# pid_driver.net
KiCad netlist of a schematic drawn in EAGLE
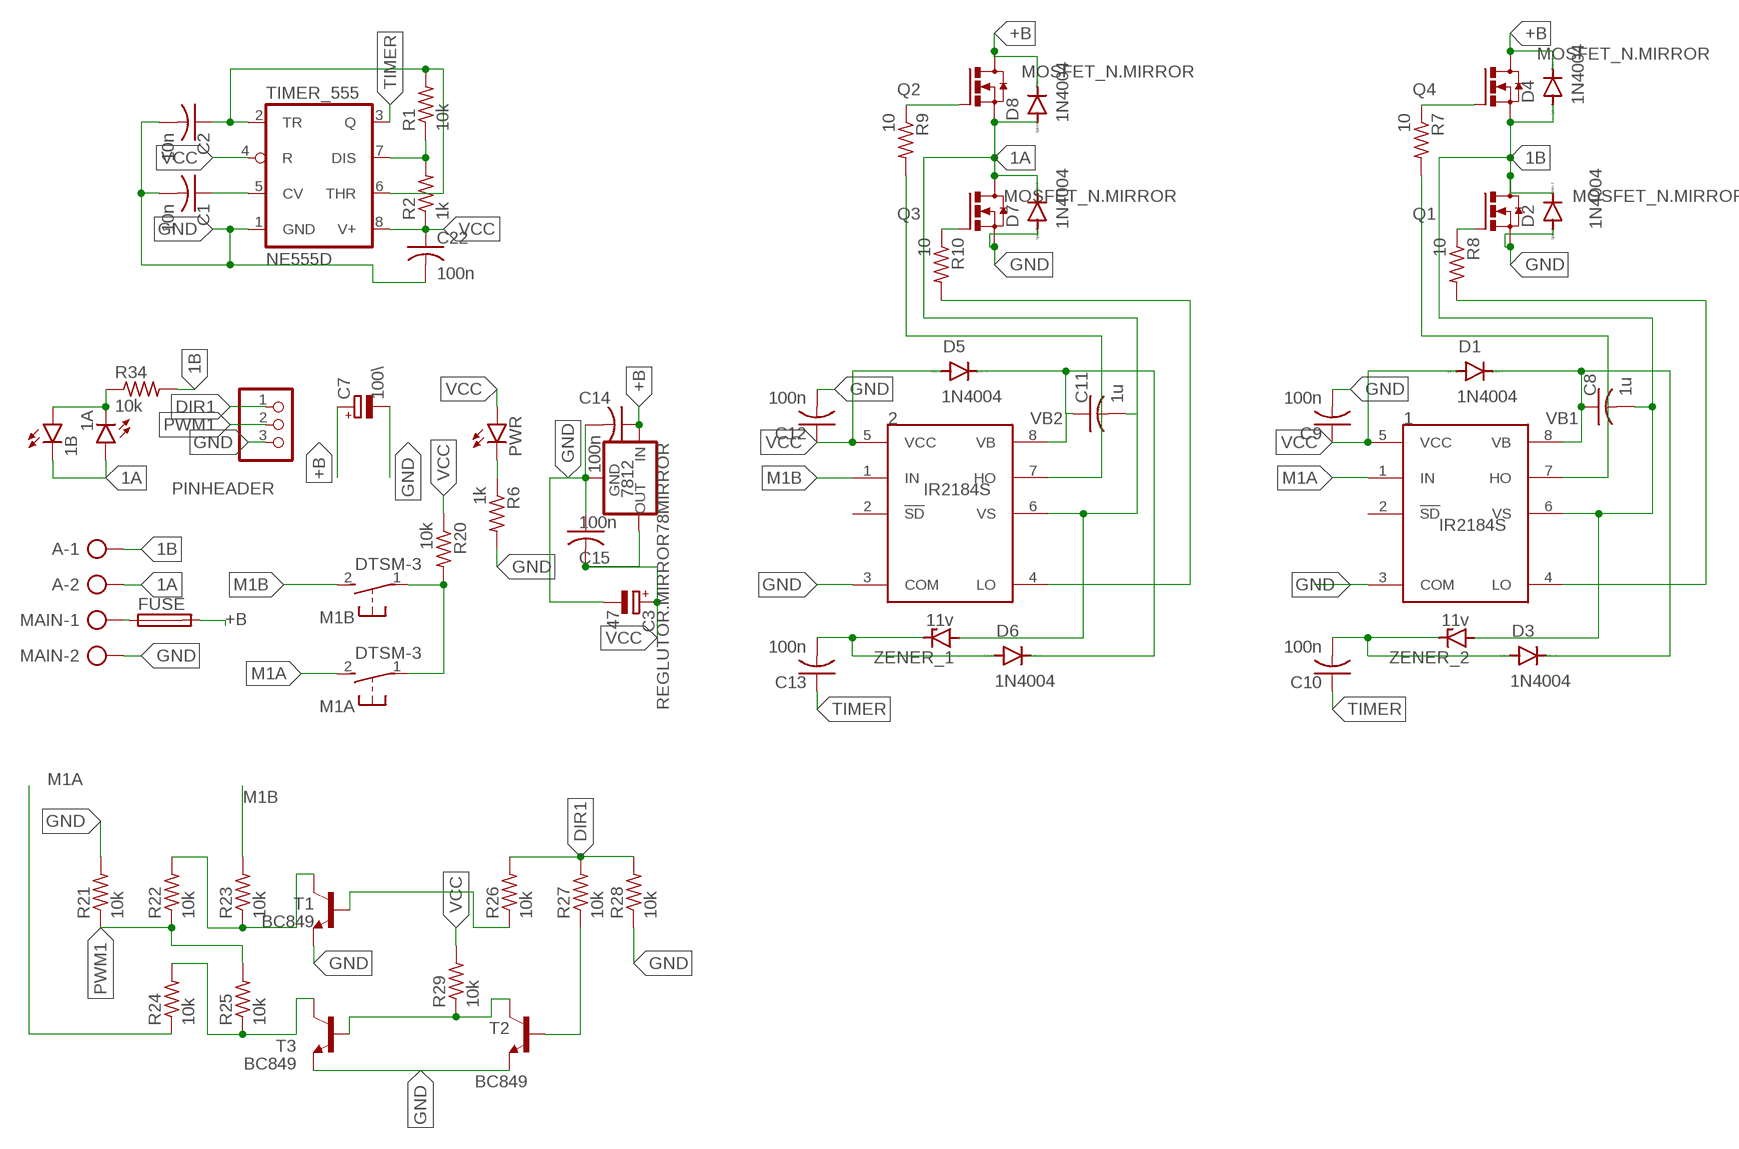
[diagram p0: schematic, sheet 1]

(export (version "E")
  (design (tool "Eeschema 10.0.6"))
  (components
    (comp (ref "1")
      (value "IR2184S")
      (footprint "eagle-import:SO08")
      (libsource (lib "eagle-import") (part "IR2184S"))
    )
    (comp (ref "1A")
      (value "LEDCHIPLED_1206")
      (footprint "eagle-import:CHIPLED_1206")
      (libsource (lib "eagle-import") (part "LEDCHIPLED_1206"))
    )
    (comp (ref "1B")
      (value "LEDCHIPLED_1206")
      (footprint "eagle-import:CHIPLED_1206")
      (libsource (lib "eagle-import") (part "LEDCHIPLED_1206"))
    )
    (comp (ref "2")
      (value "IR2184S")
      (footprint "eagle-import:SO08")
      (libsource (lib "eagle-import") (part "IR2184S"))
    )
    (comp (ref "7812")
      (value "REGLUTOR.MIRROR78MIRROR")
      (footprint "eagle-import:78MIRROR")
      (libsource (lib "eagle-import") (part "REGLUTOR.MIRROR78MIRROR"))
    )
    (comp (ref "A")
      (value "AK300/22")
      (footprint "eagle-import:XTALRR488W60L1090T465H350B")
      (libsource (lib "eagle-import") (part "AK300/22"))
    )
    (comp (ref "C1")
      (value "10n")
      (footprint "eagle-import:C1206K")
      (libsource (lib "eagle-import") (part "C-USC1206K"))
    )
    (comp (ref "C2")
      (value "10n")
      (footprint "eagle-import:C1206K")
      (libsource (lib "eagle-import") (part "C-USC1206K"))
    )
    (comp (ref "C3")
      (value "47")
      (footprint "eagle-import:E5-10,5")
      (libsource (lib "eagle-import") (part "CPOL-EUE5-10.5"))
    )
    (comp (ref "C7")
      (value "100\\")
      (footprint "eagle-import:E5-10,5")
      (libsource (lib "eagle-import") (part "CPOL-EUE5-10.5"))
    )
    (comp (ref "C8")
      (value "1u")
      (footprint "eagle-import:C1206K")
      (libsource (lib "eagle-import") (part "C-USC1206K"))
    )
    (comp (ref "C9")
      (value "100n")
      (footprint "eagle-import:C1206K")
      (libsource (lib "eagle-import") (part "C-USC1206K"))
    )
    (comp (ref "C10")
      (value "100n")
      (footprint "eagle-import:C1206K")
      (libsource (lib "eagle-import") (part "C-USC1206K"))
    )
    (comp (ref "C11")
      (value "1u")
      (footprint "eagle-import:C1206K")
      (libsource (lib "eagle-import") (part "C-USC1206K"))
    )
    (comp (ref "C12")
      (value "100n")
      (footprint "eagle-import:C1206K")
      (libsource (lib "eagle-import") (part "C-USC1206K"))
    )
    (comp (ref "C13")
      (value "100n")
      (footprint "eagle-import:C1206K")
      (libsource (lib "eagle-import") (part "C-USC1206K"))
    )
    (comp (ref "C14")
      (value "100n")
      (footprint "eagle-import:C1206K")
      (libsource (lib "eagle-import") (part "C-USC1206K"))
    )
    (comp (ref "C15")
      (value "100n")
      (footprint "eagle-import:C1206K")
      (libsource (lib "eagle-import") (part "C-USC1206K"))
    )
    (comp (ref "C22")
      (value "100n")
      (footprint "eagle-import:C1206K")
      (libsource (lib "eagle-import") (part "C-USC1206K"))
    )
    (comp (ref "D1")
      (value "1N4004")
      (footprint "eagle-import:DO41-10")
      (libsource (lib "eagle-import") (part "1N4004"))
    )
    (comp (ref "D2")
      (value "1N4004")
      (footprint "eagle-import:DO41-10")
      (libsource (lib "eagle-import") (part "1N4004"))
    )
    (comp (ref "D3")
      (value "1N4004")
      (footprint "eagle-import:DO41-10")
      (libsource (lib "eagle-import") (part "1N4004"))
    )
    (comp (ref "D4")
      (value "1N4004")
      (footprint "eagle-import:DO41-10")
      (libsource (lib "eagle-import") (part "1N4004"))
    )
    (comp (ref "D5")
      (value "1N4004")
      (footprint "eagle-import:DO41-10")
      (libsource (lib "eagle-import") (part "1N4004"))
    )
    (comp (ref "D6")
      (value "1N4004")
      (footprint "eagle-import:DO41-10")
      (libsource (lib "eagle-import") (part "1N4004"))
    )
    (comp (ref "D7")
      (value "1N4004")
      (footprint "eagle-import:DO41-10")
      (libsource (lib "eagle-import") (part "1N4004"))
    )
    (comp (ref "D8")
      (value "1N4004")
      (footprint "eagle-import:DO41-10")
      (libsource (lib "eagle-import") (part "1N4004"))
    )
    (comp (ref "FUSE")
      (value "FUSE_HOLDER")
      (footprint "eagle-import:SH22,5A")
      (libsource (lib "eagle-import") (part "FUSE_HOLDER"))
    )
    (comp (ref "M1A")
      (value "DTSM-3")
      (footprint "eagle-import:DTSM-3")
      (libsource (lib "eagle-import") (part "DTSM-3"))
    )
    (comp (ref "M1B")
      (value "DTSM-3")
      (footprint "eagle-import:DTSM-3")
      (libsource (lib "eagle-import") (part "DTSM-3"))
    )
    (comp (ref "MAIN")
      (value "AK300/22")
      (footprint "eagle-import:XTALRR488W60L1090T465H350B")
      (libsource (lib "eagle-import") (part "AK300/22"))
    )
    (comp (ref "PINHEADER")
      (value "PINHD-1X3")
      (footprint "eagle-import:1X03")
      (libsource (lib "eagle-import") (part "PINHD-1X3"))
    )
    (comp (ref "PWR")
      (value "LEDCHIPLED_1206")
      (footprint "eagle-import:CHIPLED_1206")
      (libsource (lib "eagle-import") (part "LEDCHIPLED_1206"))
    )
    (comp (ref "Q1")
      (value "MOSFET_N.MIRROR")
      (footprint "eagle-import:TO220.MIRROR")
      (libsource (lib "eagle-import") (part "MOSFET_N.MIRROR"))
    )
    (comp (ref "Q2")
      (value "MOSFET_N.MIRROR")
      (footprint "eagle-import:TO220.MIRROR")
      (libsource (lib "eagle-import") (part "MOSFET_N.MIRROR"))
    )
    (comp (ref "Q3")
      (value "MOSFET_N.MIRROR")
      (footprint "eagle-import:TO220.MIRROR")
      (libsource (lib "eagle-import") (part "MOSFET_N.MIRROR"))
    )
    (comp (ref "Q4")
      (value "MOSFET_N.MIRROR")
      (footprint "eagle-import:TO220.MIRROR")
      (libsource (lib "eagle-import") (part "MOSFET_N.MIRROR"))
    )
    (comp (ref "R1")
      (value "10k")
      (footprint "eagle-import:M1206")
      (libsource (lib "eagle-import") (part "R-US_M1206"))
    )
    (comp (ref "R2")
      (value "1k")
      (footprint "eagle-import:M1206")
      (libsource (lib "eagle-import") (part "R-US_M1206"))
    )
    (comp (ref "R6")
      (value "1k")
      (footprint "eagle-import:M1206")
      (libsource (lib "eagle-import") (part "R-US_M1206"))
    )
    (comp (ref "R7")
      (value "10")
      (footprint "eagle-import:M1206")
      (libsource (lib "eagle-import") (part "R-US_M1206"))
    )
    (comp (ref "R8")
      (value "10")
      (footprint "eagle-import:M1206")
      (libsource (lib "eagle-import") (part "R-US_M1206"))
    )
    (comp (ref "R9")
      (value "10")
      (footprint "eagle-import:M1206")
      (libsource (lib "eagle-import") (part "R-US_M1206"))
    )
    (comp (ref "R10")
      (value "10")
      (footprint "eagle-import:M1206")
      (libsource (lib "eagle-import") (part "R-US_M1206"))
    )
    (comp (ref "R20")
      (value "10k")
      (footprint "eagle-import:M1206")
      (libsource (lib "eagle-import") (part "R-US_M1206"))
    )
    (comp (ref "R21")
      (value "10k")
      (footprint "eagle-import:R1206")
      (libsource (lib "eagle-import") (part "R-US_R1206"))
    )
    (comp (ref "R22")
      (value "10k")
      (footprint "eagle-import:R1206")
      (libsource (lib "eagle-import") (part "R-US_R1206"))
    )
    (comp (ref "R23")
      (value "10k")
      (footprint "eagle-import:R1206")
      (libsource (lib "eagle-import") (part "R-US_R1206"))
    )
    (comp (ref "R24")
      (value "10k")
      (footprint "eagle-import:R1206")
      (libsource (lib "eagle-import") (part "R-US_R1206"))
    )
    (comp (ref "R25")
      (value "10k")
      (footprint "eagle-import:R1206")
      (libsource (lib "eagle-import") (part "R-US_R1206"))
    )
    (comp (ref "R26")
      (value "10k")
      (footprint "eagle-import:R1206")
      (libsource (lib "eagle-import") (part "R-US_R1206"))
    )
    (comp (ref "R27")
      (value "10k")
      (footprint "eagle-import:R1206")
      (libsource (lib "eagle-import") (part "R-US_R1206"))
    )
    (comp (ref "R28")
      (value "10k")
      (footprint "eagle-import:R1206")
      (libsource (lib "eagle-import") (part "R-US_R1206"))
    )
    (comp (ref "R29")
      (value "10k")
      (footprint "eagle-import:R1206")
      (libsource (lib "eagle-import") (part "R-US_R1206"))
    )
    (comp (ref "R34")
      (value "10k")
      (footprint "eagle-import:M1206")
      (libsource (lib "eagle-import") (part "R-US_M1206"))
    )
    (comp (ref "T1")
      (value "BC849")
      (footprint "eagle-import:SOT23")
      (libsource (lib "eagle-import") (part "BC849"))
    )
    (comp (ref "T2")
      (value "BC849")
      (footprint "eagle-import:SOT23")
      (libsource (lib "eagle-import") (part "BC849"))
    )
    (comp (ref "T3")
      (value "BC849")
      (footprint "eagle-import:SOT23")
      (libsource (lib "eagle-import") (part "BC849"))
    )
    (comp (ref "TIMER_555")
      (value "NE555D")
      (footprint "eagle-import:SO08")
      (libsource (lib "eagle-import") (part "555DNE"))
    )
    (comp (ref "ZENER_1")
      (value "11v")
      (footprint "eagle-import:SOD81")
      (libsource (lib "eagle-import") (part "BZD23"))
    )
    (comp (ref "ZENER_2")
      (value "11v")
      (footprint "eagle-import:SOD81")
      (libsource (lib "eagle-import") (part "BZD23"))
    )
  )
  (nets
    (net (code "1") (name "+B") (class "Default")
      (node (ref "7812") (pin "IN") (pinfunction "IN_IN") (pintype "input"))
      (node (ref "C14") (pin "1") (pinfunction "1_1") (pintype "passive"))
      (node (ref "C7") (pin "+") (pinfunction "+_+") (pintype "passive"))
      (node (ref "D4") (pin "C") (pinfunction "C_C") (pintype "passive"))
      (node (ref "D8") (pin "C") (pinfunction "C_C") (pintype "passive"))
      (node (ref "FUSE") (pin "2") (pinfunction "2_2") (pintype "passive"))
      (node (ref "Q2") (pin "D") (pinfunction "D_D") (pintype "passive"))
      (node (ref "Q4") (pin "D") (pinfunction "D_D") (pintype "passive"))
    )
    (net (code "2") (name "1A") (class "Default")
      (node (ref "1A") (pin "A") (pinfunction "A_A") (pintype "passive"))
      (node (ref "1B") (pin "C") (pinfunction "C_C") (pintype "passive"))
      (node (ref "2") (pin "6") (pinfunction "VS_6") (pintype "power_in"))
      (node (ref "A") (pin "2") (pinfunction "KL_2") (pintype "passive"))
      (node (ref "C11") (pin "2") (pinfunction "2_2") (pintype "passive"))
      (node (ref "D7") (pin "C") (pinfunction "C_C") (pintype "passive"))
      (node (ref "D8") (pin "A") (pinfunction "A_A") (pintype "passive"))
      (node (ref "Q2") (pin "S") (pinfunction "S_S") (pintype "passive"))
      (node (ref "Q3") (pin "D") (pinfunction "D_D") (pintype "passive"))
      (node (ref "ZENER_1") (pin "A") (pinfunction "A_A") (pintype "passive"))
    )
    (net (code "3") (name "1B") (class "Default")
      (node (ref "1") (pin "6") (pinfunction "VS_6") (pintype "power_in"))
      (node (ref "A") (pin "1") (pinfunction "KL_1") (pintype "passive"))
      (node (ref "C8") (pin "2") (pinfunction "2_2") (pintype "passive"))
      (node (ref "D2") (pin "C") (pinfunction "C_C") (pintype "passive"))
      (node (ref "D4") (pin "A") (pinfunction "A_A") (pintype "passive"))
      (node (ref "Q1") (pin "D") (pinfunction "D_D") (pintype "passive"))
      (node (ref "Q4") (pin "S") (pinfunction "S_S") (pintype "passive"))
      (node (ref "R34") (pin "2") (pinfunction "2_2") (pintype "passive"))
      (node (ref "ZENER_2") (pin "A") (pinfunction "A_A") (pintype "passive"))
    )
    (net (code "4") (name "DIR1") (class "Default")
      (node (ref "PINHEADER") (pin "1") (pinfunction "1_1") (pintype "passive"))
      (node (ref "R26") (pin "2") (pinfunction "2_2") (pintype "passive"))
      (node (ref "R27") (pin "2") (pinfunction "2_2") (pintype "passive"))
      (node (ref "R28") (pin "2") (pinfunction "2_2") (pintype "passive"))
    )
    (net (code "5") (name "GND") (class "Default")
      (node (ref "1") (pin "3") (pinfunction "COM_3") (pintype "power_in"))
      (node (ref "2") (pin "3") (pinfunction "COM_3") (pintype "power_in"))
      (node (ref "7812") (pin "GND") (pinfunction "GND_GND") (pintype "input"))
      (node (ref "C1") (pin "2") (pinfunction "2_2") (pintype "passive"))
      (node (ref "C12") (pin "2") (pinfunction "2_2") (pintype "passive"))
      (node (ref "C14") (pin "2") (pinfunction "2_2") (pintype "passive"))
      (node (ref "C15") (pin "1") (pinfunction "1_1") (pintype "passive"))
      (node (ref "C2") (pin "2") (pinfunction "2_2") (pintype "passive"))
      (node (ref "C22") (pin "2") (pinfunction "2_2") (pintype "passive"))
      (node (ref "C3") (pin "-") (pinfunction "-_-") (pintype "passive"))
      (node (ref "C7") (pin "-") (pinfunction "-_-") (pintype "passive"))
      (node (ref "C9") (pin "2") (pinfunction "2_2") (pintype "passive"))
      (node (ref "D2") (pin "A") (pinfunction "A_A") (pintype "passive"))
      (node (ref "D7") (pin "A") (pinfunction "A_A") (pintype "passive"))
      (node (ref "MAIN") (pin "2") (pinfunction "KL_2") (pintype "passive"))
      (node (ref "PINHEADER") (pin "3") (pinfunction "3_3") (pintype "passive"))
      (node (ref "Q1") (pin "S") (pinfunction "S_S") (pintype "passive"))
      (node (ref "Q3") (pin "S") (pinfunction "S_S") (pintype "passive"))
      (node (ref "R21") (pin "2") (pinfunction "2_2") (pintype "passive"))
      (node (ref "R28") (pin "1") (pinfunction "1_1") (pintype "passive"))
      (node (ref "R6") (pin "2") (pinfunction "2_2") (pintype "passive"))
      (node (ref "T1") (pin "2") (pinfunction "E_2") (pintype "passive"))
      (node (ref "T2") (pin "2") (pinfunction "E_2") (pintype "passive"))
      (node (ref "T3") (pin "2") (pinfunction "E_2") (pintype "passive"))
      (node (ref "TIMER_555") (pin "1") (pinfunction "GND_1") (pintype "power_in"))
    )
    (net (code "6") (name "M1A") (class "Default")
      (node (ref "1") (pin "1") (pinfunction "IN_1") (pintype "input"))
      (node (ref "M1A") (pin "2") (pinfunction "2_2") (pintype "passive"))
      (node (ref "R24") (pin "1") (pinfunction "1_1") (pintype "passive"))
    )
    (net (code "7") (name "M1B") (class "Default")
      (node (ref "2") (pin "1") (pinfunction "IN_1") (pintype "input"))
      (node (ref "M1B") (pin "2") (pinfunction "2_2") (pintype "passive"))
      (node (ref "R23") (pin "2") (pinfunction "2_2") (pintype "passive"))
    )
    (net (code "8") (name "Net-(1-HO)") (class "Default")
      (node (ref "1") (pin "7") (pinfunction "HO_7") (pintype "output"))
      (node (ref "R7") (pin "2") (pinfunction "2_2") (pintype "passive"))
    )
    (net (code "9") (name "Net-(1-LO)") (class "Default")
      (node (ref "1") (pin "4") (pinfunction "LO_4") (pintype "output"))
      (node (ref "R8") (pin "2") (pinfunction "2_2") (pintype "passive"))
    )
    (net (code "10") (name "Net-(1A-PadC)") (class "Default")
      (node (ref "1A") (pin "C") (pinfunction "C_C") (pintype "passive"))
      (node (ref "1B") (pin "A") (pinfunction "A_A") (pintype "passive"))
      (node (ref "R34") (pin "1") (pinfunction "1_1") (pintype "passive"))
    )
    (net (code "11") (name "Net-(2-HO)") (class "Default")
      (node (ref "2") (pin "7") (pinfunction "HO_7") (pintype "output"))
      (node (ref "R9") (pin "2") (pinfunction "2_2") (pintype "passive"))
    )
    (net (code "12") (name "Net-(2-LO)") (class "Default")
      (node (ref "2") (pin "4") (pinfunction "LO_4") (pintype "output"))
      (node (ref "R10") (pin "2") (pinfunction "2_2") (pintype "passive"))
    )
    (net (code "13") (name "Net-(C10-Pad2)") (class "Default")
      (node (ref "C10") (pin "2") (pinfunction "2_2") (pintype "passive"))
      (node (ref "D3") (pin "A") (pinfunction "A_A") (pintype "passive"))
      (node (ref "ZENER_2") (pin "C") (pinfunction "C_C") (pintype "passive"))
    )
    (net (code "14") (name "Net-(C13-Pad2)") (class "Default")
      (node (ref "C13") (pin "2") (pinfunction "2_2") (pintype "passive"))
      (node (ref "D6") (pin "A") (pinfunction "A_A") (pintype "passive"))
      (node (ref "ZENER_1") (pin "C") (pinfunction "C_C") (pintype "passive"))
    )
    (net (code "15") (name "Net-(M1A-Pad1)") (class "Default")
      (node (ref "M1A") (pin "1") (pinfunction "1_1") (pintype "passive"))
      (node (ref "M1B") (pin "1") (pinfunction "1_1") (pintype "passive"))
      (node (ref "R20") (pin "2") (pinfunction "2_2") (pintype "passive"))
    )
    (net (code "16") (name "Net-(MAINA-KL)") (class "Default")
      (node (ref "FUSE") (pin "1") (pinfunction "1_1") (pintype "passive"))
      (node (ref "MAIN") (pin "1") (pinfunction "KL_1") (pintype "passive"))
    )
    (net (code "17") (name "Net-(PWR-PadC)") (class "Default")
      (node (ref "PWR") (pin "C") (pinfunction "C_C") (pintype "passive"))
      (node (ref "R6") (pin "1") (pinfunction "1_1") (pintype "passive"))
    )
    (net (code "18") (name "Net-(Q1-PadG)") (class "Default")
      (node (ref "Q1") (pin "G") (pinfunction "G_G") (pintype "passive"))
      (node (ref "R8") (pin "1") (pinfunction "1_1") (pintype "passive"))
    )
    (net (code "19") (name "Net-(Q2-PadG)") (class "Default")
      (node (ref "Q2") (pin "G") (pinfunction "G_G") (pintype "passive"))
      (node (ref "R9") (pin "1") (pinfunction "1_1") (pintype "passive"))
    )
    (net (code "20") (name "Net-(Q3-PadG)") (class "Default")
      (node (ref "Q3") (pin "G") (pinfunction "G_G") (pintype "passive"))
      (node (ref "R10") (pin "1") (pinfunction "1_1") (pintype "passive"))
    )
    (net (code "21") (name "Net-(Q4-PadG)") (class "Default")
      (node (ref "Q4") (pin "G") (pinfunction "G_G") (pintype "passive"))
      (node (ref "R7") (pin "1") (pinfunction "1_1") (pintype "passive"))
    )
    (net (code "22") (name "Net-(T1-B)") (class "Default")
      (node (ref "R26") (pin "1") (pinfunction "1_1") (pintype "passive"))
      (node (ref "T1") (pin "1") (pinfunction "B_1") (pintype "passive"))
    )
    (net (code "23") (name "Net-(T1-C)") (class "Default")
      (node (ref "R22") (pin "2") (pinfunction "2_2") (pintype "passive"))
      (node (ref "R23") (pin "1") (pinfunction "1_1") (pintype "passive"))
      (node (ref "T1") (pin "3") (pinfunction "C_3") (pintype "passive"))
    )
    (net (code "24") (name "Net-(T2-B)") (class "Default")
      (node (ref "R27") (pin "1") (pinfunction "1_1") (pintype "passive"))
      (node (ref "T2") (pin "1") (pinfunction "B_1") (pintype "passive"))
    )
    (net (code "25") (name "Net-(T2-C)") (class "Default")
      (node (ref "R29") (pin "1") (pinfunction "1_1") (pintype "passive"))
      (node (ref "T2") (pin "3") (pinfunction "C_3") (pintype "passive"))
      (node (ref "T3") (pin "1") (pinfunction "B_1") (pintype "passive"))
    )
    (net (code "26") (name "Net-(T3-C)") (class "Default")
      (node (ref "R24") (pin "2") (pinfunction "2_2") (pintype "passive"))
      (node (ref "R25") (pin "1") (pinfunction "1_1") (pintype "passive"))
      (node (ref "T3") (pin "3") (pinfunction "C_3") (pintype "passive"))
    )
    (net (code "27") (name "Net-(TIMER_555-CV)") (class "Default")
      (node (ref "C1") (pin "1") (pinfunction "1_1") (pintype "passive"))
      (node (ref "TIMER_555") (pin "5") (pinfunction "CV_5") (pintype "input"))
    )
    (net (code "28") (name "Net-(TIMER_555-DIS)") (class "Default")
      (node (ref "R1") (pin "1") (pinfunction "1_1") (pintype "passive"))
      (node (ref "R2") (pin "2") (pinfunction "2_2") (pintype "passive"))
      (node (ref "TIMER_555") (pin "7") (pinfunction "DIS_7") (pintype "input"))
    )
    (net (code "29") (name "Net-(TIMER_555-THR)") (class "Default")
      (node (ref "C2") (pin "1") (pinfunction "1_1") (pintype "passive"))
      (node (ref "R1") (pin "2") (pinfunction "2_2") (pintype "passive"))
      (node (ref "TIMER_555") (pin "2") (pinfunction "TR_2") (pintype "input"))
      (node (ref "TIMER_555") (pin "6") (pinfunction "THR_6") (pintype "input"))
    )
    (net (code "30") (name "PWM1") (class "Default")
      (node (ref "PINHEADER") (pin "2") (pinfunction "2_2") (pintype "passive"))
      (node (ref "R21") (pin "1") (pinfunction "1_1") (pintype "passive"))
      (node (ref "R22") (pin "1") (pinfunction "1_1") (pintype "passive"))
      (node (ref "R25") (pin "2") (pinfunction "2_2") (pintype "passive"))
    )
    (net (code "31") (name "TIMER") (class "Default")
      (node (ref "C10") (pin "1") (pinfunction "1_1") (pintype "passive"))
      (node (ref "C13") (pin "1") (pinfunction "1_1") (pintype "passive"))
      (node (ref "TIMER_555") (pin "3") (pinfunction "Q_3") (pintype "output"))
    )
    (net (code "32") (name "VB1") (class "Default")
      (node (ref "1") (pin "8") (pinfunction "VB_8") (pintype "power_in"))
      (node (ref "C8") (pin "1") (pinfunction "1_1") (pintype "passive"))
      (node (ref "D1") (pin "C") (pinfunction "C_C") (pintype "passive"))
      (node (ref "D3") (pin "C") (pinfunction "C_C") (pintype "passive"))
    )
    (net (code "33") (name "VB2") (class "Default")
      (node (ref "2") (pin "8") (pinfunction "VB_8") (pintype "power_in"))
      (node (ref "C11") (pin "1") (pinfunction "1_1") (pintype "passive"))
      (node (ref "D5") (pin "C") (pinfunction "C_C") (pintype "passive"))
      (node (ref "D6") (pin "C") (pinfunction "C_C") (pintype "passive"))
    )
    (net (code "34") (name "VCC") (class "Default")
      (node (ref "1") (pin "5") (pinfunction "VCC_5") (pintype "power_in"))
      (node (ref "2") (pin "5") (pinfunction "VCC_5") (pintype "power_in"))
      (node (ref "7812") (pin "OUT") (pinfunction "OUT_OUT") (pintype "passive"))
      (node (ref "C12") (pin "1") (pinfunction "1_1") (pintype "passive"))
      (node (ref "C15") (pin "2") (pinfunction "2_2") (pintype "passive"))
      (node (ref "C22") (pin "1") (pinfunction "1_1") (pintype "passive"))
      (node (ref "C3") (pin "+") (pinfunction "+_+") (pintype "passive"))
      (node (ref "C9") (pin "1") (pinfunction "1_1") (pintype "passive"))
      (node (ref "D1") (pin "A") (pinfunction "A_A") (pintype "passive"))
      (node (ref "D5") (pin "A") (pinfunction "A_A") (pintype "passive"))
      (node (ref "PWR") (pin "A") (pinfunction "A_A") (pintype "passive"))
      (node (ref "R2") (pin "1") (pinfunction "1_1") (pintype "passive"))
      (node (ref "R20") (pin "1") (pinfunction "1_1") (pintype "passive"))
      (node (ref "R29") (pin "2") (pinfunction "2_2") (pintype "passive"))
      (node (ref "TIMER_555") (pin "4") (pinfunction "R_4") (pintype "input"))
      (node (ref "TIMER_555") (pin "8") (pinfunction "V+_8") (pintype "power_in"))
    )
    (net (code "35") (name "unconnected-(1-~{SD}-Pad2)") (class "Default")
      (node (ref "1") (pin "2") (pinfunction "~{SD}_2") (pintype "input"))
    )
    (net (code "36") (name "unconnected-(2-~{SD}-Pad2)") (class "Default")
      (node (ref "2") (pin "2") (pinfunction "~{SD}_2") (pintype "input"))
    )
  )
)
